# clock-digits.net
KiCad netlist of a schematic drawn in EAGLE
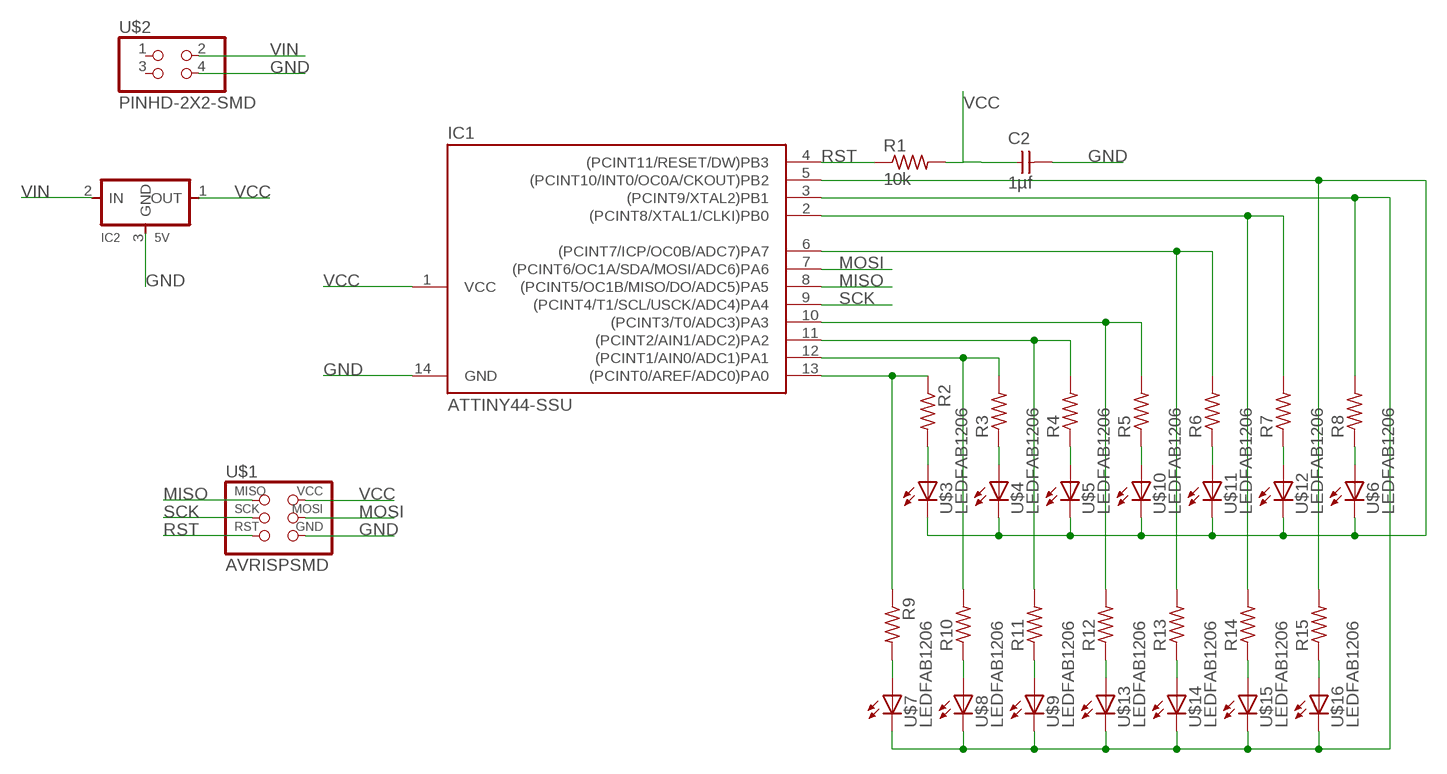
[diagram p0: schematic, sheet 1]

(export (version "E")
  (design (tool "Eeschema 10.0.6"))
  (components
    (comp (ref "C2")
      (value "1µf")
      (footprint "eagle-import:C1206FAB")
      (libsource (lib "eagle-import") (part "CAP-UNPOLARIZEDFAB"))
    )
    (comp (ref "IC1")
      (value "ATTINY44-SSU")
      (footprint "eagle-import:SOIC14")
      (libsource (lib "eagle-import") (part "ATTINY44-SSU"))
    )
    (comp (ref "IC2")
      (value "5V")
      (footprint "eagle-import:SOT23")
      (libsource (lib "eagle-import") (part "REGULATORSOT23"))
    )
    (comp (ref "R1")
      (value "10k")
      (footprint "eagle-import:R1206FAB")
      (libsource (lib "eagle-import") (part "RES-US1206FAB"))
    )
    (comp (ref "R2")
      (value "RES-US1206FAB")
      (footprint "eagle-import:R1206FAB")
      (libsource (lib "eagle-import") (part "RES-US1206FAB"))
    )
    (comp (ref "R3")
      (value "RES-US1206FAB")
      (footprint "eagle-import:R1206FAB")
      (libsource (lib "eagle-import") (part "RES-US1206FAB"))
    )
    (comp (ref "R4")
      (value "RES-US1206FAB")
      (footprint "eagle-import:R1206FAB")
      (libsource (lib "eagle-import") (part "RES-US1206FAB"))
    )
    (comp (ref "R5")
      (value "RES-US1206FAB")
      (footprint "eagle-import:R1206FAB")
      (libsource (lib "eagle-import") (part "RES-US1206FAB"))
    )
    (comp (ref "R6")
      (value "RES-US1206FAB")
      (footprint "eagle-import:R1206FAB")
      (libsource (lib "eagle-import") (part "RES-US1206FAB"))
    )
    (comp (ref "R7")
      (value "RES-US1206FAB")
      (footprint "eagle-import:R1206FAB")
      (libsource (lib "eagle-import") (part "RES-US1206FAB"))
    )
    (comp (ref "R8")
      (value "RES-US1206FAB")
      (footprint "eagle-import:R1206FAB")
      (libsource (lib "eagle-import") (part "RES-US1206FAB"))
    )
    (comp (ref "R9")
      (value "RES-US1206FAB")
      (footprint "eagle-import:R1206FAB")
      (libsource (lib "eagle-import") (part "RES-US1206FAB"))
    )
    (comp (ref "R10")
      (value "RES-US1206FAB")
      (footprint "eagle-import:R1206FAB")
      (libsource (lib "eagle-import") (part "RES-US1206FAB"))
    )
    (comp (ref "R11")
      (value "RES-US1206FAB")
      (footprint "eagle-import:R1206FAB")
      (libsource (lib "eagle-import") (part "RES-US1206FAB"))
    )
    (comp (ref "R12")
      (value "RES-US1206FAB")
      (footprint "eagle-import:R1206FAB")
      (libsource (lib "eagle-import") (part "RES-US1206FAB"))
    )
    (comp (ref "R13")
      (value "RES-US1206FAB")
      (footprint "eagle-import:R1206FAB")
      (libsource (lib "eagle-import") (part "RES-US1206FAB"))
    )
    (comp (ref "R14")
      (value "RES-US1206FAB")
      (footprint "eagle-import:R1206FAB")
      (libsource (lib "eagle-import") (part "RES-US1206FAB"))
    )
    (comp (ref "R15")
      (value "RES-US1206FAB")
      (footprint "eagle-import:R1206FAB")
      (libsource (lib "eagle-import") (part "RES-US1206FAB"))
    )
    (comp (ref "U$1")
      (value "AVRISPSMD")
      (footprint "eagle-import:2X03SMD")
      (libsource (lib "eagle-import") (part "AVRISPSMD"))
    )
    (comp (ref "U$2")
      (value "PINHD-2X2-SMD")
      (footprint "eagle-import:2X02SMD")
      (libsource (lib "eagle-import") (part "PINHD-2X2-SMD"))
    )
    (comp (ref "U$3")
      (value "LEDFAB1206")
      (footprint "eagle-import:LED1206FAB")
      (libsource (lib "eagle-import") (part "LEDFAB1206"))
    )
    (comp (ref "U$4")
      (value "LEDFAB1206")
      (footprint "eagle-import:LED1206FAB")
      (libsource (lib "eagle-import") (part "LEDFAB1206"))
    )
    (comp (ref "U$5")
      (value "LEDFAB1206")
      (footprint "eagle-import:LED1206FAB")
      (libsource (lib "eagle-import") (part "LEDFAB1206"))
    )
    (comp (ref "U$6")
      (value "LEDFAB1206")
      (footprint "eagle-import:LED1206FAB")
      (libsource (lib "eagle-import") (part "LEDFAB1206"))
    )
    (comp (ref "U$7")
      (value "LEDFAB1206")
      (footprint "eagle-import:LED1206FAB")
      (libsource (lib "eagle-import") (part "LEDFAB1206"))
    )
    (comp (ref "U$8")
      (value "LEDFAB1206")
      (footprint "eagle-import:LED1206FAB")
      (libsource (lib "eagle-import") (part "LEDFAB1206"))
    )
    (comp (ref "U$9")
      (value "LEDFAB1206")
      (footprint "eagle-import:LED1206FAB")
      (libsource (lib "eagle-import") (part "LEDFAB1206"))
    )
    (comp (ref "U$10")
      (value "LEDFAB1206")
      (footprint "eagle-import:LED1206FAB")
      (libsource (lib "eagle-import") (part "LEDFAB1206"))
    )
    (comp (ref "U$11")
      (value "LEDFAB1206")
      (footprint "eagle-import:LED1206FAB")
      (libsource (lib "eagle-import") (part "LEDFAB1206"))
    )
    (comp (ref "U$12")
      (value "LEDFAB1206")
      (footprint "eagle-import:LED1206FAB")
      (libsource (lib "eagle-import") (part "LEDFAB1206"))
    )
    (comp (ref "U$13")
      (value "LEDFAB1206")
      (footprint "eagle-import:LED1206FAB")
      (libsource (lib "eagle-import") (part "LEDFAB1206"))
    )
    (comp (ref "U$14")
      (value "LEDFAB1206")
      (footprint "eagle-import:LED1206FAB")
      (libsource (lib "eagle-import") (part "LEDFAB1206"))
    )
    (comp (ref "U$15")
      (value "LEDFAB1206")
      (footprint "eagle-import:LED1206FAB")
      (libsource (lib "eagle-import") (part "LEDFAB1206"))
    )
    (comp (ref "U$16")
      (value "LEDFAB1206")
      (footprint "eagle-import:LED1206FAB")
      (libsource (lib "eagle-import") (part "LEDFAB1206"))
    )
  )
  (nets
    (net (code "1") (name "/GND") (class "Default")
      (node (ref "C2") (pin "2") (pinfunction "2_2") (pintype "passive"))
      (node (ref "IC1") (pin "14") (pinfunction "GND_14") (pintype "power_in"))
      (node (ref "IC2") (pin "3") (pinfunction "GND_3") (pintype "bidirectional"))
      (node (ref "U$1") (pin "6") (pinfunction "GND_6") (pintype "passive"))
      (node (ref "U$2") (pin "4") (pinfunction "4_4") (pintype "passive"))
    )
    (net (code "2") (name "/MISO") (class "Default")
      (node (ref "IC1") (pin "8") (pinfunction "(PCINT5/OC1B/MISO/DO/ADC5)PA5_8") (pintype "bidirectional"))
      (node (ref "U$1") (pin "1") (pinfunction "MISO_1") (pintype "passive"))
    )
    (net (code "3") (name "/MOSI") (class "Default")
      (node (ref "IC1") (pin "7") (pinfunction "(PCINT6/OC1A/SDA/MOSI/ADC6)PA6_7") (pintype "bidirectional"))
      (node (ref "U$1") (pin "4") (pinfunction "MOSI_4") (pintype "passive"))
    )
    (net (code "4") (name "/RST") (class "Default")
      (node (ref "IC1") (pin "4") (pinfunction "(PCINT11/RESET/DW)PB3_4") (pintype "bidirectional"))
      (node (ref "R1") (pin "1") (pinfunction "1_1") (pintype "passive"))
      (node (ref "U$1") (pin "5") (pinfunction "RST_5") (pintype "passive"))
    )
    (net (code "5") (name "/SCK") (class "Default")
      (node (ref "IC1") (pin "9") (pinfunction "(PCINT4/T1/SCL/USCK/ADC4)PA4_9") (pintype "bidirectional"))
      (node (ref "U$1") (pin "3") (pinfunction "SCK_3") (pintype "passive"))
    )
    (net (code "6") (name "/VCC") (class "Default")
      (node (ref "IC1") (pin "1") (pinfunction "VCC_1") (pintype "power_in"))
      (node (ref "IC2") (pin "1") (pinfunction "OUT_1") (pintype "bidirectional"))
      (node (ref "R1") (pin "2") (pinfunction "2_2") (pintype "passive"))
      (node (ref "U$1") (pin "2") (pinfunction "VCC_2") (pintype "passive"))
    )
    (net (code "7") (name "/VIN") (class "Default")
      (node (ref "IC2") (pin "2") (pinfunction "IN_2") (pintype "bidirectional"))
      (node (ref "U$2") (pin "2") (pinfunction "2_2") (pintype "passive"))
    )
    (net (code "8") (name "Net-(IC1-(PCINT0{slash}AREF{slash}ADC0)PA0)") (class "Default")
      (node (ref "IC1") (pin "13") (pinfunction "(PCINT0/AREF/ADC0)PA0_13") (pintype "bidirectional"))
      (node (ref "R2") (pin "1") (pinfunction "1_1") (pintype "passive"))
      (node (ref "R9") (pin "1") (pinfunction "1_1") (pintype "passive"))
    )
    (net (code "9") (name "Net-(IC1-(PCINT1{slash}AIN0{slash}ADC1)PA1)") (class "Default")
      (node (ref "IC1") (pin "12") (pinfunction "(PCINT1/AIN0/ADC1)PA1_12") (pintype "bidirectional"))
      (node (ref "R10") (pin "2") (pinfunction "2_2") (pintype "passive"))
      (node (ref "R3") (pin "2") (pinfunction "2_2") (pintype "passive"))
    )
    (net (code "10") (name "Net-(IC1-(PCINT2{slash}AIN1{slash}ADC2)PA2)") (class "Default")
      (node (ref "IC1") (pin "11") (pinfunction "(PCINT2/AIN1/ADC2)PA2_11") (pintype "bidirectional"))
      (node (ref "R11") (pin "2") (pinfunction "2_2") (pintype "passive"))
      (node (ref "R4") (pin "2") (pinfunction "2_2") (pintype "passive"))
    )
    (net (code "11") (name "Net-(IC1-(PCINT3{slash}T0{slash}ADC3)PA3)") (class "Default")
      (node (ref "IC1") (pin "10") (pinfunction "(PCINT3/T0/ADC3)PA3_10") (pintype "bidirectional"))
      (node (ref "R12") (pin "2") (pinfunction "2_2") (pintype "passive"))
      (node (ref "R5") (pin "2") (pinfunction "2_2") (pintype "passive"))
    )
    (net (code "12") (name "Net-(IC1-(PCINT7{slash}ICP{slash}OC0B{slash}ADC7)PA7)") (class "Default")
      (node (ref "IC1") (pin "6") (pinfunction "(PCINT7/ICP/OC0B/ADC7)PA7_6") (pintype "bidirectional"))
      (node (ref "R13") (pin "2") (pinfunction "2_2") (pintype "passive"))
      (node (ref "R6") (pin "2") (pinfunction "2_2") (pintype "passive"))
    )
    (net (code "13") (name "Net-(IC1-(PCINT8{slash}XTAL1{slash}CLKI)PB0)") (class "Default")
      (node (ref "IC1") (pin "2") (pinfunction "(PCINT8/XTAL1/CLKI)PB0_2") (pintype "bidirectional"))
      (node (ref "R14") (pin "2") (pinfunction "2_2") (pintype "passive"))
      (node (ref "R7") (pin "2") (pinfunction "2_2") (pintype "passive"))
    )
    (net (code "14") (name "Net-(IC1-(PCINT9{slash}XTAL2)PB1)") (class "Default")
      (node (ref "IC1") (pin "3") (pinfunction "(PCINT9/XTAL2)PB1_3") (pintype "bidirectional"))
      (node (ref "R8") (pin "2") (pinfunction "2_2") (pintype "passive"))
      (node (ref "U$13") (pin "2") (pinfunction "C_2") (pintype "passive"))
      (node (ref "U$14") (pin "2") (pinfunction "C_2") (pintype "passive"))
      (node (ref "U$15") (pin "2") (pinfunction "C_2") (pintype "passive"))
      (node (ref "U$16") (pin "2") (pinfunction "C_2") (pintype "passive"))
      (node (ref "U$7") (pin "2") (pinfunction "C_2") (pintype "passive"))
      (node (ref "U$8") (pin "2") (pinfunction "C_2") (pintype "passive"))
      (node (ref "U$9") (pin "2") (pinfunction "C_2") (pintype "passive"))
    )
    (net (code "15") (name "Net-(IC1-(PCINT10{slash}INT0{slash}OC0A{slash}CKOUT)PB2)") (class "Default")
      (node (ref "IC1") (pin "5") (pinfunction "(PCINT10/INT0/OC0A/CKOUT)PB2_5") (pintype "bidirectional"))
      (node (ref "R15") (pin "2") (pinfunction "2_2") (pintype "passive"))
      (node (ref "U$10") (pin "2") (pinfunction "C_2") (pintype "passive"))
      (node (ref "U$11") (pin "2") (pinfunction "C_2") (pintype "passive"))
      (node (ref "U$12") (pin "2") (pinfunction "C_2") (pintype "passive"))
      (node (ref "U$3") (pin "2") (pinfunction "C_2") (pintype "passive"))
      (node (ref "U$4") (pin "2") (pinfunction "C_2") (pintype "passive"))
      (node (ref "U$5") (pin "2") (pinfunction "C_2") (pintype "passive"))
      (node (ref "U$6") (pin "2") (pinfunction "C_2") (pintype "passive"))
    )
    (net (code "16") (name "Net-(U$3-A)") (class "Default")
      (node (ref "R2") (pin "2") (pinfunction "2_2") (pintype "passive"))
      (node (ref "U$3") (pin "1") (pinfunction "A_1") (pintype "passive"))
    )
    (net (code "17") (name "Net-(U$4-A)") (class "Default")
      (node (ref "R3") (pin "1") (pinfunction "1_1") (pintype "passive"))
      (node (ref "U$4") (pin "1") (pinfunction "A_1") (pintype "passive"))
    )
    (net (code "18") (name "Net-(U$5-A)") (class "Default")
      (node (ref "R4") (pin "1") (pinfunction "1_1") (pintype "passive"))
      (node (ref "U$5") (pin "1") (pinfunction "A_1") (pintype "passive"))
    )
    (net (code "19") (name "Net-(U$6-A)") (class "Default")
      (node (ref "R8") (pin "1") (pinfunction "1_1") (pintype "passive"))
      (node (ref "U$6") (pin "1") (pinfunction "A_1") (pintype "passive"))
    )
    (net (code "20") (name "Net-(U$7-A)") (class "Default")
      (node (ref "R9") (pin "2") (pinfunction "2_2") (pintype "passive"))
      (node (ref "U$7") (pin "1") (pinfunction "A_1") (pintype "passive"))
    )
    (net (code "21") (name "Net-(U$8-A)") (class "Default")
      (node (ref "R10") (pin "1") (pinfunction "1_1") (pintype "passive"))
      (node (ref "U$8") (pin "1") (pinfunction "A_1") (pintype "passive"))
    )
    (net (code "22") (name "Net-(U$9-A)") (class "Default")
      (node (ref "R11") (pin "1") (pinfunction "1_1") (pintype "passive"))
      (node (ref "U$9") (pin "1") (pinfunction "A_1") (pintype "passive"))
    )
    (net (code "23") (name "Net-(U$10-A)") (class "Default")
      (node (ref "R5") (pin "1") (pinfunction "1_1") (pintype "passive"))
      (node (ref "U$10") (pin "1") (pinfunction "A_1") (pintype "passive"))
    )
    (net (code "24") (name "Net-(U$11-A)") (class "Default")
      (node (ref "R6") (pin "1") (pinfunction "1_1") (pintype "passive"))
      (node (ref "U$11") (pin "1") (pinfunction "A_1") (pintype "passive"))
    )
    (net (code "25") (name "Net-(U$12-A)") (class "Default")
      (node (ref "R7") (pin "1") (pinfunction "1_1") (pintype "passive"))
      (node (ref "U$12") (pin "1") (pinfunction "A_1") (pintype "passive"))
    )
    (net (code "26") (name "Net-(U$13-A)") (class "Default")
      (node (ref "R12") (pin "1") (pinfunction "1_1") (pintype "passive"))
      (node (ref "U$13") (pin "1") (pinfunction "A_1") (pintype "passive"))
    )
    (net (code "27") (name "Net-(U$14-A)") (class "Default")
      (node (ref "R13") (pin "1") (pinfunction "1_1") (pintype "passive"))
      (node (ref "U$14") (pin "1") (pinfunction "A_1") (pintype "passive"))
    )
    (net (code "28") (name "Net-(U$15-A)") (class "Default")
      (node (ref "R14") (pin "1") (pinfunction "1_1") (pintype "passive"))
      (node (ref "U$15") (pin "1") (pinfunction "A_1") (pintype "passive"))
    )
    (net (code "29") (name "Net-(U$16-A)") (class "Default")
      (node (ref "R15") (pin "1") (pinfunction "1_1") (pintype "passive"))
      (node (ref "U$16") (pin "1") (pinfunction "A_1") (pintype "passive"))
    )
    (net (code "30") (name "unconnected-(C2-Pad1)") (class "Default")
      (node (ref "C2") (pin "1") (pinfunction "1_1") (pintype "passive"))
    )
    (net (code "31") (name "unconnected-(U$2-Pad1)") (class "Default")
      (node (ref "U$2") (pin "1") (pinfunction "1_1") (pintype "passive"))
    )
    (net (code "32") (name "unconnected-(U$2-Pad3)") (class "Default")
      (node (ref "U$2") (pin "3") (pinfunction "3_3") (pintype "passive"))
    )
  )
)
